# Stereo_VCA.net
KiCad netlist of a schematic drawn in EAGLE
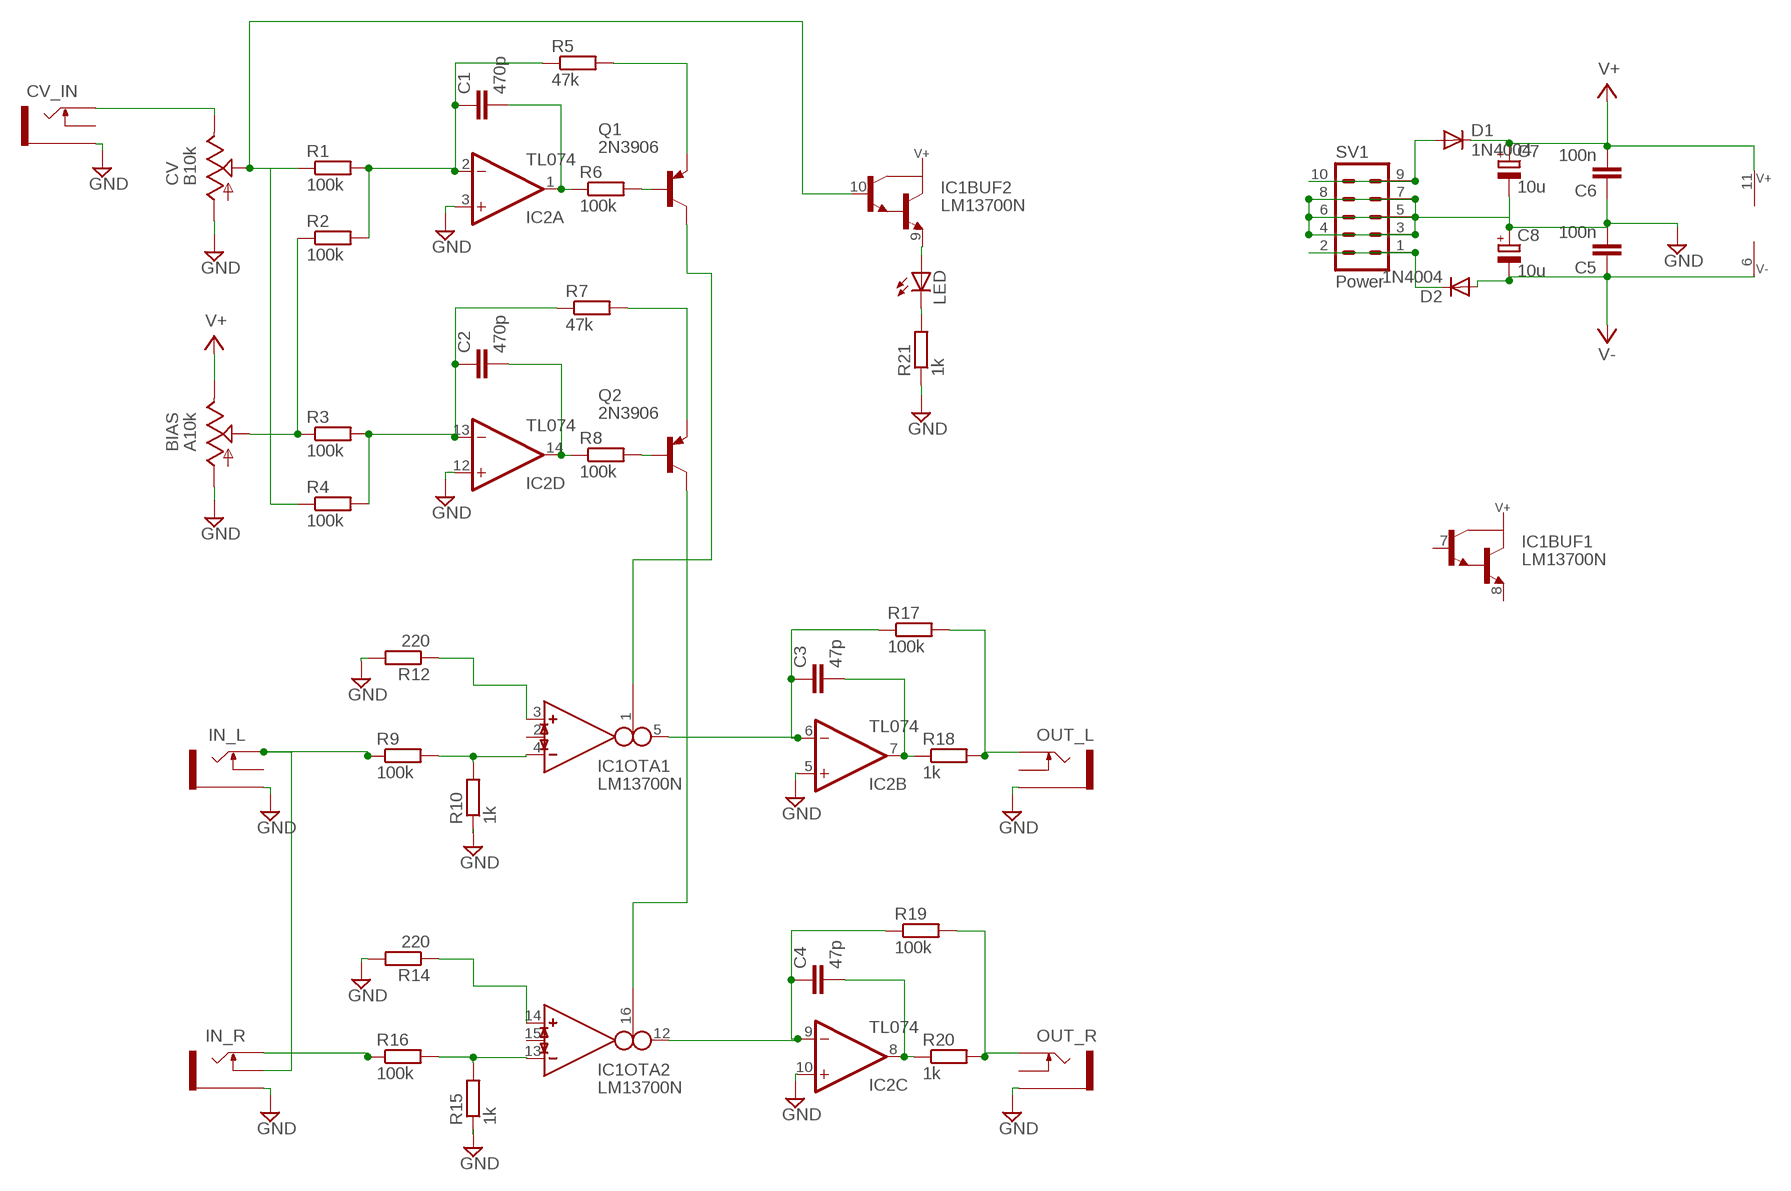
[diagram p0: schematic, sheet 1]

(export (version "E")
  (design (tool "Eeschema 10.0.6"))
  (components
    (comp (ref "BIAS")
      (value "A10k")
      (footprint "eagle-import:EVUE")
      (libsource (lib "eagle-import") (part "US-EVUE2A"))
    )
    (comp (ref "C1")
      (value "470p")
      (footprint "eagle-import:C050-024X044")
      (libsource (lib "eagle-import") (part "C-EU050-024X044"))
    )
    (comp (ref "C2")
      (value "470p")
      (footprint "eagle-import:C050-024X044")
      (libsource (lib "eagle-import") (part "C-EU050-024X044"))
    )
    (comp (ref "C3")
      (value "47p")
      (footprint "eagle-import:C050-024X044")
      (libsource (lib "eagle-import") (part "C-EU050-024X044"))
    )
    (comp (ref "C4")
      (value "47p")
      (footprint "eagle-import:C050-024X044")
      (libsource (lib "eagle-import") (part "C-EU050-024X044"))
    )
    (comp (ref "C5")
      (value "100n")
      (footprint "eagle-import:C050-024X044")
      (libsource (lib "eagle-import") (part "C-EU050-024X044"))
    )
    (comp (ref "C6")
      (value "100n")
      (footprint "eagle-import:C050-024X044")
      (libsource (lib "eagle-import") (part "C-EU050-024X044"))
    )
    (comp (ref "C7")
      (value "10u")
      (footprint "eagle-import:E3,5-8")
      (libsource (lib "eagle-import") (part "CPOL-EUE3.5-8"))
    )
    (comp (ref "C8")
      (value "10u")
      (footprint "eagle-import:E3,5-8")
      (libsource (lib "eagle-import") (part "CPOL-EUE3.5-8"))
    )
    (comp (ref "CV")
      (value "B10k")
      (footprint "eagle-import:EVUE")
      (libsource (lib "eagle-import") (part "US-EVUE2A"))
    )
    (comp (ref "CV_IN")
      (value "PJ302M")
      (footprint "eagle-import:PJ302M")
      (libsource (lib "eagle-import") (part "PJ302M"))
    )
    (comp (ref "D1")
      (value "1N4004")
      (footprint "eagle-import:DO41-10")
      (libsource (lib "eagle-import") (part "1N4004"))
    )
    (comp (ref "D2")
      (value "1N4004")
      (footprint "eagle-import:DO41-10")
      (libsource (lib "eagle-import") (part "1N4004"))
    )
    (comp (ref "IC1")
      (value "LM13700N")
      (footprint "eagle-import:DIL16")
      (libsource (lib "eagle-import") (part "LM13700N"))
    )
    (comp (ref "IC2")
      (value "TL074")
      (footprint "eagle-import:DIL14")
      (libsource (lib "eagle-import") (part "TL074_"))
    )
    (comp (ref "IN_L")
      (value "PJ302M")
      (footprint "eagle-import:PJ302M")
      (libsource (lib "eagle-import") (part "PJ302M"))
    )
    (comp (ref "IN_R")
      (value "PJ302M")
      (footprint "eagle-import:PJ302M")
      (libsource (lib "eagle-import") (part "PJ302M"))
    )
    (comp (ref "LED")
      (value "LED3MM")
      (footprint "eagle-import:LED3MM")
      (libsource (lib "eagle-import") (part "LED3MM"))
    )
    (comp (ref "OUT_L")
      (value "PJ302M")
      (footprint "eagle-import:PJ302M")
      (libsource (lib "eagle-import") (part "PJ302M"))
    )
    (comp (ref "OUT_R")
      (value "PJ302M")
      (footprint "eagle-import:PJ302M")
      (libsource (lib "eagle-import") (part "PJ302M"))
    )
    (comp (ref "Q1")
      (value "2N3906")
      (footprint "eagle-import:TO92")
      (libsource (lib "eagle-import") (part "2N3906"))
    )
    (comp (ref "Q2")
      (value "2N3906")
      (footprint "eagle-import:TO92")
      (libsource (lib "eagle-import") (part "2N3906"))
    )
    (comp (ref "R1")
      (value "100k")
      (footprint "eagle-import:0204_7")
      (libsource (lib "eagle-import") (part "R-EU_0204/7"))
    )
    (comp (ref "R2")
      (value "100k")
      (footprint "eagle-import:0204_7")
      (libsource (lib "eagle-import") (part "R-EU_0204/7"))
    )
    (comp (ref "R3")
      (value "100k")
      (footprint "eagle-import:0204_7")
      (libsource (lib "eagle-import") (part "R-EU_0204/7"))
    )
    (comp (ref "R4")
      (value "100k")
      (footprint "eagle-import:0204_7")
      (libsource (lib "eagle-import") (part "R-EU_0204/7"))
    )
    (comp (ref "R5")
      (value "47k")
      (footprint "eagle-import:0204_7")
      (libsource (lib "eagle-import") (part "R-EU_0204/7"))
    )
    (comp (ref "R6")
      (value "100k")
      (footprint "eagle-import:0204_7")
      (libsource (lib "eagle-import") (part "R-EU_0204/7"))
    )
    (comp (ref "R7")
      (value "47k")
      (footprint "eagle-import:0204_7")
      (libsource (lib "eagle-import") (part "R-EU_0204/7"))
    )
    (comp (ref "R8")
      (value "100k")
      (footprint "eagle-import:0204_7")
      (libsource (lib "eagle-import") (part "R-EU_0204/7"))
    )
    (comp (ref "R9")
      (value "100k")
      (footprint "eagle-import:0204_7")
      (libsource (lib "eagle-import") (part "R-EU_0204/7"))
    )
    (comp (ref "R10")
      (value "1k")
      (footprint "eagle-import:0204_7")
      (libsource (lib "eagle-import") (part "R-EU_0204/7"))
    )
    (comp (ref "R12")
      (value "220")
      (footprint "eagle-import:0204_7")
      (libsource (lib "eagle-import") (part "R-EU_0204/7"))
    )
    (comp (ref "R14")
      (value "220")
      (footprint "eagle-import:0204_7")
      (libsource (lib "eagle-import") (part "R-EU_0204/7"))
    )
    (comp (ref "R15")
      (value "1k")
      (footprint "eagle-import:0204_7")
      (libsource (lib "eagle-import") (part "R-EU_0204/7"))
    )
    (comp (ref "R16")
      (value "100k")
      (footprint "eagle-import:0204_7")
      (libsource (lib "eagle-import") (part "R-EU_0204/7"))
    )
    (comp (ref "R17")
      (value "100k")
      (footprint "eagle-import:0204_7")
      (libsource (lib "eagle-import") (part "R-EU_0204/7"))
    )
    (comp (ref "R18")
      (value "1k")
      (footprint "eagle-import:0204_7")
      (libsource (lib "eagle-import") (part "R-EU_0204/7"))
    )
    (comp (ref "R19")
      (value "100k")
      (footprint "eagle-import:0204_7")
      (libsource (lib "eagle-import") (part "R-EU_0204/7"))
    )
    (comp (ref "R20")
      (value "1k")
      (footprint "eagle-import:0204_7")
      (libsource (lib "eagle-import") (part "R-EU_0204/7"))
    )
    (comp (ref "R21")
      (value "1k")
      (footprint "eagle-import:0204_7")
      (libsource (lib "eagle-import") (part "R-EU_0204/7"))
    )
    (comp (ref "SV1")
      (value "Power")
      (footprint "eagle-import:EURO_PWR_HEADER_FAT")
      (libsource (lib "eagle-import") (part "EURO_POWER_HEADERFAT_PADS"))
    )
  )
  (nets
    (net (code "1") (name "GND") (class "Default")
      (node (ref "BIAS") (pin "1") (pinfunction "A_1") (pintype "passive"))
      (node (ref "C5") (pin "2") (pinfunction "2_2") (pintype "passive"))
      (node (ref "C6") (pin "1") (pinfunction "1_1") (pintype "passive"))
      (node (ref "C7") (pin "-") (pinfunction "-_-") (pintype "passive"))
      (node (ref "C8") (pin "+") (pinfunction "+_+") (pintype "passive"))
      (node (ref "CV") (pin "1") (pinfunction "A_1") (pintype "passive"))
      (node (ref "CV_IN") (pin "GND") (pinfunction "SLEEVE_GND") (pintype "passive"))
      (node (ref "IC2") (pin "10") (pinfunction "+IN_10") (pintype "input"))
      (node (ref "IC2") (pin "12") (pinfunction "+IN_12") (pintype "input"))
      (node (ref "IC2") (pin "3") (pinfunction "+IN_3") (pintype "input"))
      (node (ref "IC2") (pin "5") (pinfunction "+IN_5") (pintype "input"))
      (node (ref "IN_L") (pin "GND") (pinfunction "SLEEVE_GND") (pintype "passive"))
      (node (ref "IN_R") (pin "GND") (pinfunction "SLEEVE_GND") (pintype "passive"))
      (node (ref "OUT_L") (pin "GND") (pinfunction "SLEEVE_GND") (pintype "passive"))
      (node (ref "OUT_R") (pin "GND") (pinfunction "SLEEVE_GND") (pintype "passive"))
      (node (ref "R10") (pin "1") (pinfunction "1_1") (pintype "passive"))
      (node (ref "R12") (pin "2") (pinfunction "2_2") (pintype "passive"))
      (node (ref "R14") (pin "2") (pinfunction "2_2") (pintype "passive"))
      (node (ref "R15") (pin "1") (pinfunction "1_1") (pintype "passive"))
      (node (ref "R21") (pin "1") (pinfunction "1_1") (pintype "passive"))
      (node (ref "SV1") (pin "3") (pinfunction "3_3") (pintype "passive"))
      (node (ref "SV1") (pin "4") (pinfunction "4_4") (pintype "passive"))
      (node (ref "SV1") (pin "5") (pinfunction "5_5") (pintype "passive"))
      (node (ref "SV1") (pin "6") (pinfunction "6_6") (pintype "passive"))
      (node (ref "SV1") (pin "7") (pinfunction "7_7") (pintype "passive"))
      (node (ref "SV1") (pin "8") (pinfunction "8_8") (pintype "passive"))
    )
    (net (code "2") (name "Net-(BIAS-S)") (class "Default")
      (node (ref "BIAS") (pin "2") (pinfunction "S_2") (pintype "passive"))
      (node (ref "R2") (pin "1") (pinfunction "1_1") (pintype "passive"))
      (node (ref "R3") (pin "1") (pinfunction "1_1") (pintype "passive"))
    )
    (net (code "3") (name "Net-(CV-E)") (class "Default")
      (node (ref "CV") (pin "3") (pinfunction "E_3") (pintype "passive"))
      (node (ref "CV_IN") (pin "TIP") (pinfunction "TIP_TIP") (pintype "passive"))
    )
    (net (code "4") (name "Net-(CV-S)") (class "Default")
      (node (ref "CV") (pin "2") (pinfunction "S_2") (pintype "passive"))
      (node (ref "IC1") (pin "10") (pinfunction "B_10") (pintype "passive"))
      (node (ref "R1") (pin "1") (pinfunction "1_1") (pintype "passive"))
      (node (ref "R4") (pin "1") (pinfunction "1_1") (pintype "passive"))
    )
    (net (code "5") (name "Net-(D1-PadA)") (class "Default")
      (node (ref "D1") (pin "A") (pinfunction "A_A") (pintype "passive"))
      (node (ref "SV1") (pin "10") (pinfunction "10_10") (pintype "passive"))
      (node (ref "SV1") (pin "9") (pinfunction "9_9") (pintype "passive"))
    )
    (net (code "6") (name "Net-(D2-PadC)") (class "Default")
      (node (ref "D2") (pin "C") (pinfunction "C_C") (pintype "passive"))
      (node (ref "SV1") (pin "1") (pinfunction "1_1") (pintype "passive"))
      (node (ref "SV1") (pin "2") (pinfunction "2_2") (pintype "passive"))
    )
    (net (code "7") (name "Net-(IC1B-E)") (class "Default")
      (node (ref "IC1") (pin "9") (pinfunction "E_9") (pintype "passive"))
      (node (ref "LED") (pin "A") (pinfunction "A_A") (pintype "passive"))
    )
    (net (code "8") (name "Net-(IC1C-IN_N)") (class "Default")
      (node (ref "IC1") (pin "4") (pinfunction "IN_N_4") (pintype "input"))
      (node (ref "R10") (pin "2") (pinfunction "2_2") (pintype "passive"))
      (node (ref "R9") (pin "2") (pinfunction "2_2") (pintype "passive"))
    )
    (net (code "9") (name "Net-(IC1C-IN_P)") (class "Default")
      (node (ref "IC1") (pin "3") (pinfunction "IN_P_3") (pintype "input"))
      (node (ref "R12") (pin "1") (pinfunction "1_1") (pintype "passive"))
    )
    (net (code "10") (name "Net-(IC1C-I_BIAS)") (class "Default")
      (node (ref "IC1") (pin "1") (pinfunction "I_BIAS_1") (pintype "input"))
      (node (ref "Q1") (pin "1") (pinfunction "C_1") (pintype "passive"))
    )
    (net (code "11") (name "Net-(IC1C-OUT)") (class "Default")
      (node (ref "C3") (pin "1") (pinfunction "1_1") (pintype "passive"))
      (node (ref "IC1") (pin "5") (pinfunction "OUT_5") (pintype "output"))
      (node (ref "IC2") (pin "6") (pinfunction "-IN_6") (pintype "input"))
      (node (ref "R17") (pin "1") (pinfunction "1_1") (pintype "passive"))
    )
    (net (code "12") (name "Net-(IC1D-IN_N)") (class "Default")
      (node (ref "IC1") (pin "13") (pinfunction "IN_N_13") (pintype "input"))
      (node (ref "R15") (pin "2") (pinfunction "2_2") (pintype "passive"))
      (node (ref "R16") (pin "2") (pinfunction "2_2") (pintype "passive"))
    )
    (net (code "13") (name "Net-(IC1D-IN_P)") (class "Default")
      (node (ref "IC1") (pin "14") (pinfunction "IN_P_14") (pintype "input"))
      (node (ref "R14") (pin "1") (pinfunction "1_1") (pintype "passive"))
    )
    (net (code "14") (name "Net-(IC1D-I_BIAS)") (class "Default")
      (node (ref "IC1") (pin "16") (pinfunction "I_BIAS_16") (pintype "input"))
      (node (ref "Q2") (pin "1") (pinfunction "C_1") (pintype "passive"))
    )
    (net (code "15") (name "Net-(IC1D-OUT)") (class "Default")
      (node (ref "C4") (pin "1") (pinfunction "1_1") (pintype "passive"))
      (node (ref "IC1") (pin "12") (pinfunction "OUT_12") (pintype "output"))
      (node (ref "IC2") (pin "9") (pinfunction "-IN_9") (pintype "input"))
      (node (ref "R19") (pin "1") (pinfunction "1_1") (pintype "passive"))
    )
    (net (code "16") (name "Net-(IC2A--IN)") (class "Default")
      (node (ref "C1") (pin "1") (pinfunction "1_1") (pintype "passive"))
      (node (ref "IC2") (pin "2") (pinfunction "-IN_2") (pintype "input"))
      (node (ref "R1") (pin "2") (pinfunction "2_2") (pintype "passive"))
      (node (ref "R2") (pin "2") (pinfunction "2_2") (pintype "passive"))
      (node (ref "R5") (pin "1") (pinfunction "1_1") (pintype "passive"))
    )
    (net (code "17") (name "Net-(IC2A-OUT)") (class "Default")
      (node (ref "C1") (pin "2") (pinfunction "2_2") (pintype "passive"))
      (node (ref "IC2") (pin "1") (pinfunction "OUT_1") (pintype "output"))
      (node (ref "R6") (pin "1") (pinfunction "1_1") (pintype "passive"))
    )
    (net (code "18") (name "Net-(IC2B-OUT)") (class "Default")
      (node (ref "C3") (pin "2") (pinfunction "2_2") (pintype "passive"))
      (node (ref "IC2") (pin "7") (pinfunction "OUT_7") (pintype "output"))
      (node (ref "R18") (pin "1") (pinfunction "1_1") (pintype "passive"))
    )
    (net (code "19") (name "Net-(IC2C-OUT)") (class "Default")
      (node (ref "C4") (pin "2") (pinfunction "2_2") (pintype "passive"))
      (node (ref "IC2") (pin "8") (pinfunction "OUT_8") (pintype "output"))
      (node (ref "R20") (pin "1") (pinfunction "1_1") (pintype "passive"))
    )
    (net (code "20") (name "Net-(IC2D--IN)") (class "Default")
      (node (ref "C2") (pin "1") (pinfunction "1_1") (pintype "passive"))
      (node (ref "IC2") (pin "13") (pinfunction "-IN_13") (pintype "input"))
      (node (ref "R3") (pin "2") (pinfunction "2_2") (pintype "passive"))
      (node (ref "R4") (pin "2") (pinfunction "2_2") (pintype "passive"))
      (node (ref "R7") (pin "1") (pinfunction "1_1") (pintype "passive"))
    )
    (net (code "21") (name "Net-(IC2D-OUT)") (class "Default")
      (node (ref "C2") (pin "2") (pinfunction "2_2") (pintype "passive"))
      (node (ref "IC2") (pin "14") (pinfunction "OUT_14") (pintype "output"))
      (node (ref "R8") (pin "1") (pinfunction "1_1") (pintype "passive"))
    )
    (net (code "22") (name "Net-(IN_R-PadTIP)") (class "Default")
      (node (ref "IN_R") (pin "TIP") (pinfunction "TIP_TIP") (pintype "passive"))
      (node (ref "R16") (pin "1") (pinfunction "1_1") (pintype "passive"))
    )
    (net (code "23") (name "Net-(IN_R-SWITCH)") (class "Default")
      (node (ref "IN_L") (pin "TIP") (pinfunction "TIP_TIP") (pintype "passive"))
      (node (ref "IN_R") (pin "SW") (pinfunction "SWITCH_SW") (pintype "passive"))
      (node (ref "R9") (pin "1") (pinfunction "1_1") (pintype "passive"))
    )
    (net (code "24") (name "Net-(LED-C)") (class "Default")
      (node (ref "LED") (pin "K") (pinfunction "C_K") (pintype "passive"))
      (node (ref "R21") (pin "2") (pinfunction "2_2") (pintype "passive"))
    )
    (net (code "25") (name "Net-(OUT_L-PadTIP)") (class "Default")
      (node (ref "OUT_L") (pin "TIP") (pinfunction "TIP_TIP") (pintype "passive"))
      (node (ref "R17") (pin "2") (pinfunction "2_2") (pintype "passive"))
      (node (ref "R18") (pin "2") (pinfunction "2_2") (pintype "passive"))
    )
    (net (code "26") (name "Net-(OUT_R-PadTIP)") (class "Default")
      (node (ref "OUT_R") (pin "TIP") (pinfunction "TIP_TIP") (pintype "passive"))
      (node (ref "R19") (pin "2") (pinfunction "2_2") (pintype "passive"))
      (node (ref "R20") (pin "2") (pinfunction "2_2") (pintype "passive"))
    )
    (net (code "27") (name "Net-(Q1-B)") (class "Default")
      (node (ref "Q1") (pin "2") (pinfunction "B_2") (pintype "passive"))
      (node (ref "R6") (pin "2") (pinfunction "2_2") (pintype "passive"))
    )
    (net (code "28") (name "Net-(Q1-E)") (class "Default")
      (node (ref "Q1") (pin "3") (pinfunction "E_3") (pintype "passive"))
      (node (ref "R5") (pin "2") (pinfunction "2_2") (pintype "passive"))
    )
    (net (code "29") (name "Net-(Q2-B)") (class "Default")
      (node (ref "Q2") (pin "2") (pinfunction "B_2") (pintype "passive"))
      (node (ref "R8") (pin "2") (pinfunction "2_2") (pintype "passive"))
    )
    (net (code "30") (name "Net-(Q2-E)") (class "Default")
      (node (ref "Q2") (pin "3") (pinfunction "E_3") (pintype "passive"))
      (node (ref "R7") (pin "2") (pinfunction "2_2") (pintype "passive"))
    )
    (net (code "31") (name "V+") (class "Default")
      (node (ref "BIAS") (pin "3") (pinfunction "E_3") (pintype "passive"))
      (node (ref "C6") (pin "2") (pinfunction "2_2") (pintype "passive"))
      (node (ref "C7") (pin "+") (pinfunction "+_+") (pintype "passive"))
      (node (ref "D1") (pin "C") (pinfunction "C_C") (pintype "passive"))
      (node (ref "IC1") (pin "11") (pinfunction "V+_11") (pintype "power_in"))
    )
    (net (code "32") (name "V-") (class "Default")
      (node (ref "C5") (pin "1") (pinfunction "1_1") (pintype "passive"))
      (node (ref "C8") (pin "-") (pinfunction "-_-") (pintype "passive"))
      (node (ref "D2") (pin "A") (pinfunction "A_A") (pintype "passive"))
      (node (ref "IC1") (pin "6") (pinfunction "V-_6") (pintype "power_in"))
    )
    (net (code "33") (name "unconnected-(CV_IN-SWITCH-PadSW)") (class "Default")
      (node (ref "CV_IN") (pin "SW") (pinfunction "SWITCH_SW") (pintype "passive"))
    )
    (net (code "34") (name "unconnected-(IC1A-B-Pad7)") (class "Default")
      (node (ref "IC1") (pin "7") (pinfunction "B_7") (pintype "passive"))
    )
    (net (code "35") (name "unconnected-(IC1A-E-Pad8)") (class "Default")
      (node (ref "IC1") (pin "8") (pinfunction "E_8") (pintype "passive"))
    )
    (net (code "36") (name "unconnected-(IC1C-I_DIODE-Pad2)") (class "Default")
      (node (ref "IC1") (pin "2") (pinfunction "I_DIODE_2") (pintype "input"))
    )
    (net (code "37") (name "unconnected-(IC1D-I_DIODE-Pad15)") (class "Default")
      (node (ref "IC1") (pin "15") (pinfunction "I_DIODE_15") (pintype "input"))
    )
    (net (code "38") (name "unconnected-(IN_L-SWITCH-PadSW)") (class "Default")
      (node (ref "IN_L") (pin "SW") (pinfunction "SWITCH_SW") (pintype "passive"))
    )
    (net (code "39") (name "unconnected-(OUT_L-SWITCH-PadSW)") (class "Default")
      (node (ref "OUT_L") (pin "SW") (pinfunction "SWITCH_SW") (pintype "passive"))
    )
    (net (code "40") (name "unconnected-(OUT_R-SWITCH-PadSW)") (class "Default")
      (node (ref "OUT_R") (pin "SW") (pinfunction "SWITCH_SW") (pintype "passive"))
    )
  )
)
